# CC_Debugger.net
KiCad netlist of a schematic drawn in EAGLE
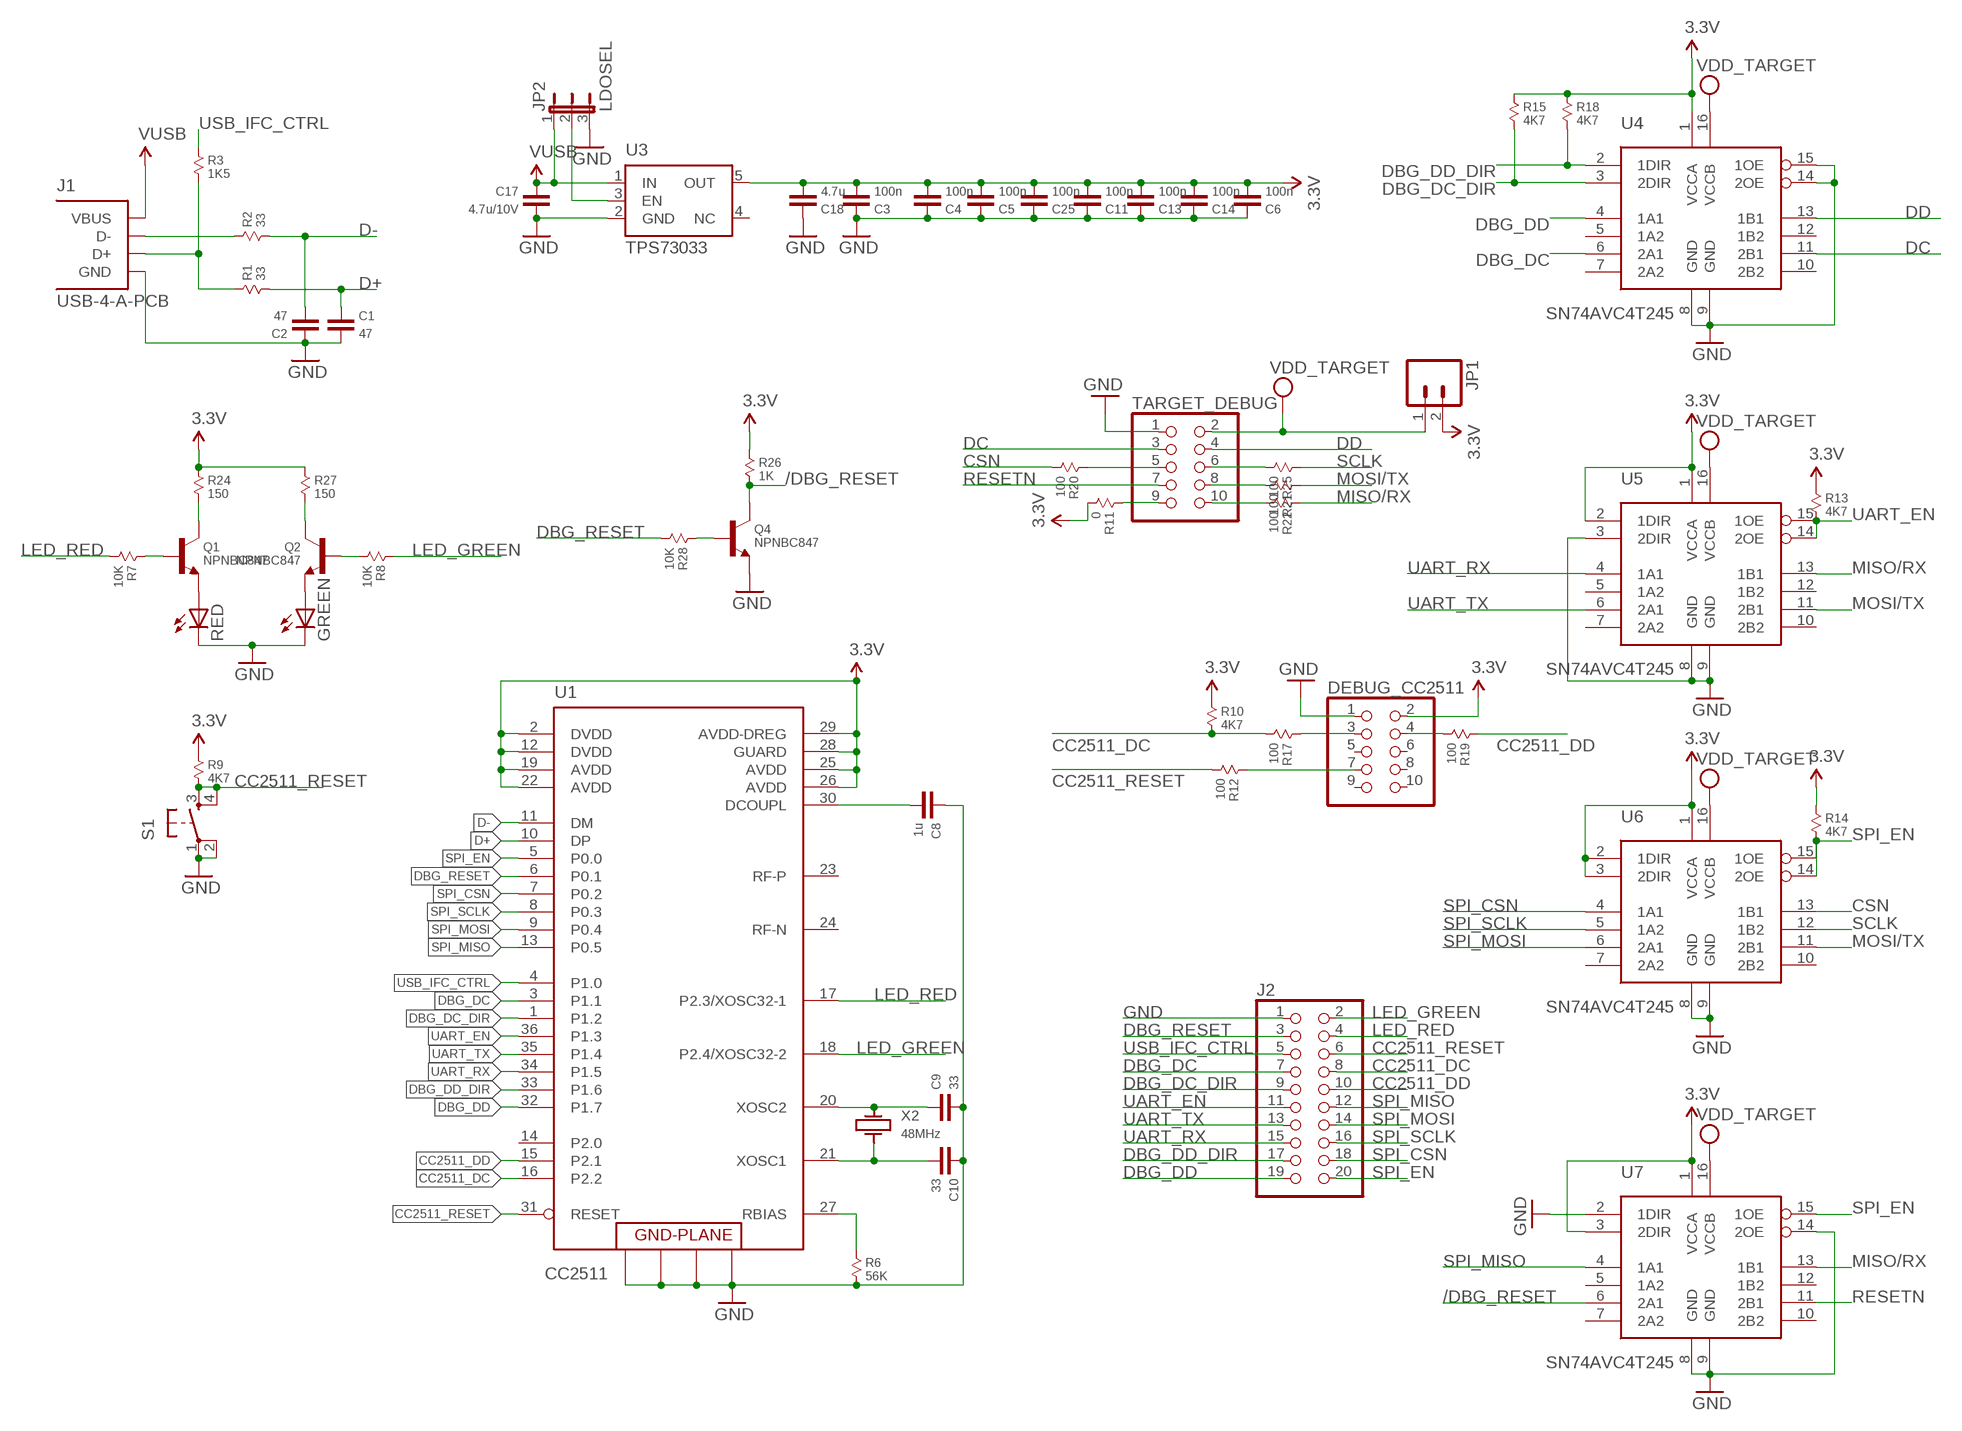
[diagram p0: schematic, sheet 1]

(export (version "E")
  (design (tool "Eeschema 10.0.6"))
  (components
    (comp (ref "C1")
      (value "47")
      (footprint "eagle-import:0603")
      (libsource (lib "eagle-import") (part "CAP-0603"))
    )
    (comp (ref "C2")
      (value "47")
      (footprint "eagle-import:0603")
      (libsource (lib "eagle-import") (part "CAP-0603"))
    )
    (comp (ref "C3")
      (value "100n")
      (footprint "eagle-import:0603")
      (libsource (lib "eagle-import") (part "CAP-0603"))
    )
    (comp (ref "C4")
      (value "100n")
      (footprint "eagle-import:0603")
      (libsource (lib "eagle-import") (part "CAP-0603"))
    )
    (comp (ref "C5")
      (value "100n")
      (footprint "eagle-import:0603")
      (libsource (lib "eagle-import") (part "CAP-0603"))
    )
    (comp (ref "C6")
      (value "100n")
      (footprint "eagle-import:0603")
      (libsource (lib "eagle-import") (part "CAP-0603"))
    )
    (comp (ref "C8")
      (value "1u")
      (footprint "eagle-import:0603")
      (libsource (lib "eagle-import") (part "CAP-0603"))
    )
    (comp (ref "C9")
      (value "33")
      (footprint "eagle-import:0603")
      (libsource (lib "eagle-import") (part "CAP-0603"))
    )
    (comp (ref "C10")
      (value "33")
      (footprint "eagle-import:0603")
      (libsource (lib "eagle-import") (part "CAP-0603"))
    )
    (comp (ref "C11")
      (value "100n")
      (footprint "eagle-import:0603")
      (libsource (lib "eagle-import") (part "CAP-0603"))
    )
    (comp (ref "C13")
      (value "100n")
      (footprint "eagle-import:0603")
      (libsource (lib "eagle-import") (part "CAP-0603"))
    )
    (comp (ref "C14")
      (value "100n")
      (footprint "eagle-import:0603")
      (libsource (lib "eagle-import") (part "CAP-0603"))
    )
    (comp (ref "C17")
      (value "4.7u/10V")
      (footprint "eagle-import:0603")
      (libsource (lib "eagle-import") (part "CAP-0603"))
    )
    (comp (ref "C18")
      (value "4.7u")
      (footprint "eagle-import:0603")
      (libsource (lib "eagle-import") (part "CAP-0603"))
    )
    (comp (ref "C25")
      (value "100n")
      (footprint "eagle-import:0603")
      (libsource (lib "eagle-import") (part "CAP-0603"))
    )
    (comp (ref "DEBUG_CC2511")
      (value "PINHD-2X5")
      (footprint "eagle-import:2X05")
      (libsource (lib "eagle-import") (part "PINHD-2X5"))
    )
    (comp (ref "GREEN")
      (value "LEDCHIPLED_0805")
      (footprint "eagle-import:CHIPLED_0805")
      (libsource (lib "eagle-import") (part "LEDCHIPLED_0805"))
    )
    (comp (ref "J1")
      (value "USB-4-A-PCB")
      (footprint "eagle-import:USB-A-PCB")
      (libsource (lib "eagle-import") (part "USB-4-A-PCB"))
    )
    (comp (ref "J2")
      (value "PINHD-2X10")
      (footprint "eagle-import:2X10")
      (libsource (lib "eagle-import") (part "PINHD-2X10"))
    )
    (comp (ref "JP1")
      (value "M02PTH")
      (footprint "eagle-import:1X02")
      (libsource (lib "eagle-import") (part "M02PTH"))
    )
    (comp (ref "JP2")
      (value "LDOSEL")
      (footprint "eagle-import:SJ_3")
      (libsource (lib "eagle-import") (part "JUMPER-3SMD"))
    )
    (comp (ref "Q1")
      (value "NPNBC847")
      (footprint "eagle-import:SOT-23")
      (libsource (lib "eagle-import") (part "NPNBC847"))
    )
    (comp (ref "Q2")
      (value "NPNBC847")
      (footprint "eagle-import:SOT-23")
      (libsource (lib "eagle-import") (part "NPNBC847"))
    )
    (comp (ref "Q4")
      (value "NPNBC847")
      (footprint "eagle-import:SOT-23")
      (libsource (lib "eagle-import") (part "NPNBC847"))
    )
    (comp (ref "R1")
      (value "33")
      (footprint "eagle-import:0603")
      (libsource (lib "eagle-import") (part "RESISTOR-0603"))
    )
    (comp (ref "R2")
      (value "33")
      (footprint "eagle-import:0603")
      (libsource (lib "eagle-import") (part "RESISTOR-0603"))
    )
    (comp (ref "R3")
      (value "1K5")
      (footprint "eagle-import:0603")
      (libsource (lib "eagle-import") (part "RESISTOR-0603"))
    )
    (comp (ref "R6")
      (value "56K")
      (footprint "eagle-import:0603")
      (libsource (lib "eagle-import") (part "RESISTOR-0603"))
    )
    (comp (ref "R7")
      (value "10K")
      (footprint "eagle-import:0603")
      (libsource (lib "eagle-import") (part "RESISTOR-0603"))
    )
    (comp (ref "R8")
      (value "10K")
      (footprint "eagle-import:0603")
      (libsource (lib "eagle-import") (part "RESISTOR-0603"))
    )
    (comp (ref "R9")
      (value "4K7")
      (footprint "eagle-import:0603")
      (libsource (lib "eagle-import") (part "RESISTOR-0603"))
    )
    (comp (ref "R10")
      (value "4K7")
      (footprint "eagle-import:0603")
      (libsource (lib "eagle-import") (part "RESISTOR-0603"))
    )
    (comp (ref "R11")
      (value "0")
      (footprint "eagle-import:0603")
      (libsource (lib "eagle-import") (part "RESISTOR-0603"))
    )
    (comp (ref "R12")
      (value "100")
      (footprint "eagle-import:0603")
      (libsource (lib "eagle-import") (part "RESISTOR-0603"))
    )
    (comp (ref "R13")
      (value "4K7")
      (footprint "eagle-import:0603")
      (libsource (lib "eagle-import") (part "RESISTOR-0603"))
    )
    (comp (ref "R14")
      (value "4K7")
      (footprint "eagle-import:0603")
      (libsource (lib "eagle-import") (part "RESISTOR-0603"))
    )
    (comp (ref "R15")
      (value "4K7")
      (footprint "eagle-import:0603")
      (libsource (lib "eagle-import") (part "RESISTOR-0603"))
    )
    (comp (ref "R17")
      (value "100")
      (footprint "eagle-import:0603")
      (libsource (lib "eagle-import") (part "RESISTOR-0603"))
    )
    (comp (ref "R18")
      (value "4K7")
      (footprint "eagle-import:0603")
      (libsource (lib "eagle-import") (part "RESISTOR-0603"))
    )
    (comp (ref "R19")
      (value "100")
      (footprint "eagle-import:0603")
      (libsource (lib "eagle-import") (part "RESISTOR-0603"))
    )
    (comp (ref "R20")
      (value "100")
      (footprint "eagle-import:0603")
      (libsource (lib "eagle-import") (part "RESISTOR-0603"))
    )
    (comp (ref "R21")
      (value "100")
      (footprint "eagle-import:0603")
      (libsource (lib "eagle-import") (part "RESISTOR-0603"))
    )
    (comp (ref "R22")
      (value "100")
      (footprint "eagle-import:0603")
      (libsource (lib "eagle-import") (part "RESISTOR-0603"))
    )
    (comp (ref "R24")
      (value "150")
      (footprint "eagle-import:0603")
      (libsource (lib "eagle-import") (part "RESISTOR-0603"))
    )
    (comp (ref "R25")
      (value "100")
      (footprint "eagle-import:0603")
      (libsource (lib "eagle-import") (part "RESISTOR-0603"))
    )
    (comp (ref "R26")
      (value "1K")
      (footprint "eagle-import:0603")
      (libsource (lib "eagle-import") (part "RESISTOR-0603"))
    )
    (comp (ref "R27")
      (value "150")
      (footprint "eagle-import:0603")
      (libsource (lib "eagle-import") (part "RESISTOR-0603"))
    )
    (comp (ref "R28")
      (value "10K")
      (footprint "eagle-import:0603")
      (libsource (lib "eagle-import") (part "RESISTOR-0603"))
    )
    (comp (ref "RED")
      (value "LEDCHIPLED_0805")
      (footprint "eagle-import:CHIPLED_0805")
      (libsource (lib "eagle-import") (part "LEDCHIPLED_0805"))
    )
    (comp (ref "S1")
      (value "TAC_SWITCHPTH")
      (footprint "eagle-import:TACTILE-PTH")
      (libsource (lib "eagle-import") (part "TAC_SWITCHPTH"))
    )
    (comp (ref "TARGET_DEBUG")
      (value "PINHD-2X5")
      (footprint "eagle-import:2X05")
      (libsource (lib "eagle-import") (part "PINHD-2X5"))
    )
    (comp (ref "U1")
      (value "CC2511")
      (footprint "eagle-import:QLP-36")
      (libsource (lib "eagle-import") (part "CC2511"))
    )
    (comp (ref "U3")
      (value "TPS73033")
      (footprint "eagle-import:SOT23-5")
      (libsource (lib "eagle-import") (part "TPS73033"))
    )
    (comp (ref "U4")
      (value "SN74AVC4T245")
      (footprint "eagle-import:TSSOP16")
      (libsource (lib "eagle-import") (part "SN74AVC4T245"))
    )
    (comp (ref "U5")
      (value "SN74AVC4T245")
      (footprint "eagle-import:TSSOP16")
      (libsource (lib "eagle-import") (part "SN74AVC4T245"))
    )
    (comp (ref "U6")
      (value "SN74AVC4T245")
      (footprint "eagle-import:TSSOP16")
      (libsource (lib "eagle-import") (part "SN74AVC4T245"))
    )
    (comp (ref "U7")
      (value "SN74AVC4T245")
      (footprint "eagle-import:TSSOP16")
      (libsource (lib "eagle-import") (part "SN74AVC4T245"))
    )
    (comp (ref "X2")
      (value "48MHz")
      (footprint "eagle-import:KX-9A")
      (libsource (lib "eagle-import") (part "CRYSTAL-KX-9A"))
    )
  )
  (nets
    (net (code "1") (name "/CSN") (class "Default")
      (node (ref "R20") (pin "2") (pinfunction "2_2") (pintype "passive"))
      (node (ref "U6") (pin "13") (pinfunction "1B1_13") (pintype "bidirectional"))
    )
    (net (code "2") (name "/DC") (class "Default")
      (node (ref "TARGET_DEBUG") (pin "3") (pinfunction "3_3") (pintype "passive"))
      (node (ref "U4") (pin "11") (pinfunction "2B1_11") (pintype "bidirectional"))
    )
    (net (code "3") (name "/DD") (class "Default")
      (node (ref "TARGET_DEBUG") (pin "4") (pinfunction "4_4") (pintype "passive"))
      (node (ref "U4") (pin "13") (pinfunction "1B1_13") (pintype "bidirectional"))
    )
    (net (code "4") (name "/LED_GREEN") (class "Default")
      (node (ref "J2") (pin "2") (pinfunction "2_2") (pintype "passive"))
      (node (ref "R8") (pin "1") (pinfunction "1_1") (pintype "passive"))
      (node (ref "U1") (pin "18") (pinfunction "P2.4/XOSC32-2_18") (pintype "passive"))
    )
    (net (code "5") (name "/LED_RED") (class "Default")
      (node (ref "J2") (pin "4") (pinfunction "4_4") (pintype "passive"))
      (node (ref "R7") (pin "2") (pinfunction "2_2") (pintype "passive"))
      (node (ref "U1") (pin "17") (pinfunction "P2.3/XOSC32-1_17") (pintype "passive"))
    )
    (net (code "6") (name "/MISO{slash}RX") (class "Default")
      (node (ref "R22") (pin "1") (pinfunction "1_1") (pintype "passive"))
      (node (ref "U5") (pin "13") (pinfunction "1B1_13") (pintype "bidirectional"))
      (node (ref "U7") (pin "13") (pinfunction "1B1_13") (pintype "bidirectional"))
    )
    (net (code "7") (name "/MOSI{slash}TX") (class "Default")
      (node (ref "R21") (pin "1") (pinfunction "1_1") (pintype "passive"))
      (node (ref "U5") (pin "11") (pinfunction "2B1_11") (pintype "bidirectional"))
      (node (ref "U6") (pin "11") (pinfunction "2B1_11") (pintype "bidirectional"))
    )
    (net (code "8") (name "/RESETN") (class "Default")
      (node (ref "TARGET_DEBUG") (pin "7") (pinfunction "7_7") (pintype "passive"))
      (node (ref "U7") (pin "11") (pinfunction "2B1_11") (pintype "bidirectional"))
    )
    (net (code "9") (name "/SCLK") (class "Default")
      (node (ref "R25") (pin "1") (pinfunction "1_1") (pintype "passive"))
      (node (ref "U6") (pin "12") (pinfunction "1B2_12") (pintype "bidirectional"))
    )
    (net (code "10") (name "/{slash}DBG_RESET") (class "Default")
      (node (ref "Q4") (pin "3") (pinfunction "C_3") (pintype "passive"))
      (node (ref "R26") (pin "2") (pinfunction "2_2") (pintype "passive"))
      (node (ref "U7") (pin "6") (pinfunction "2A1_6") (pintype "bidirectional"))
    )
    (net (code "11") (name "3.3V") (class "Default")
      (node (ref "C11") (pin "1") (pinfunction "1_1") (pintype "passive"))
      (node (ref "C13") (pin "1") (pinfunction "1_1") (pintype "passive"))
      (node (ref "C14") (pin "1") (pinfunction "1_1") (pintype "passive"))
      (node (ref "C18") (pin "1") (pinfunction "1_1") (pintype "passive"))
      (node (ref "C25") (pin "1") (pinfunction "1_1") (pintype "passive"))
      (node (ref "C3") (pin "1") (pinfunction "1_1") (pintype "passive"))
      (node (ref "C4") (pin "1") (pinfunction "1_1") (pintype "passive"))
      (node (ref "C5") (pin "1") (pinfunction "1_1") (pintype "passive"))
      (node (ref "C6") (pin "1") (pinfunction "1_1") (pintype "passive"))
      (node (ref "DEBUG_CC2511") (pin "2") (pinfunction "2_2") (pintype "passive"))
      (node (ref "JP1") (pin "2") (pinfunction "2_2") (pintype "passive"))
      (node (ref "R10") (pin "1") (pinfunction "1_1") (pintype "passive"))
      (node (ref "R11") (pin "2") (pinfunction "2_2") (pintype "passive"))
      (node (ref "R13") (pin "1") (pinfunction "1_1") (pintype "passive"))
      (node (ref "R14") (pin "1") (pinfunction "1_1") (pintype "passive"))
      (node (ref "R15") (pin "1") (pinfunction "1_1") (pintype "passive"))
      (node (ref "R18") (pin "1") (pinfunction "1_1") (pintype "passive"))
      (node (ref "R24") (pin "1") (pinfunction "1_1") (pintype "passive"))
      (node (ref "R26") (pin "1") (pinfunction "1_1") (pintype "passive"))
      (node (ref "R27") (pin "1") (pinfunction "1_1") (pintype "passive"))
      (node (ref "R9") (pin "1") (pinfunction "1_1") (pintype "passive"))
      (node (ref "U1") (pin "12") (pinfunction "DVDD_12") (pintype "passive"))
      (node (ref "U1") (pin "19") (pinfunction "AVDD_19") (pintype "passive"))
      (node (ref "U1") (pin "2") (pinfunction "DVDD_2") (pintype "passive"))
      (node (ref "U1") (pin "22") (pinfunction "AVDD_22") (pintype "passive"))
      (node (ref "U1") (pin "25") (pinfunction "AVDD_25") (pintype "passive"))
      (node (ref "U1") (pin "26") (pinfunction "AVDD_26") (pintype "passive"))
      (node (ref "U1") (pin "28") (pinfunction "GUARD_28") (pintype "passive"))
      (node (ref "U1") (pin "29") (pinfunction "AVDD-DREG_29") (pintype "passive"))
      (node (ref "U3") (pin "5") (pinfunction "OUT_5") (pintype "passive"))
      (node (ref "U4") (pin "1") (pinfunction "VCCA_1") (pintype "passive"))
      (node (ref "U5") (pin "1") (pinfunction "VCCA_1") (pintype "passive"))
      (node (ref "U5") (pin "2") (pinfunction "1DIR_2") (pintype "input"))
      (node (ref "U6") (pin "1") (pinfunction "VCCA_1") (pintype "passive"))
      (node (ref "U6") (pin "2") (pinfunction "1DIR_2") (pintype "input"))
      (node (ref "U6") (pin "3") (pinfunction "2DIR_3") (pintype "input"))
      (node (ref "U7") (pin "1") (pinfunction "VCCA_1") (pintype "passive"))
      (node (ref "U7") (pin "3") (pinfunction "2DIR_3") (pintype "input"))
    )
    (net (code "12") (name "CC2511_DC") (class "Default")
      (node (ref "J2") (pin "8") (pinfunction "8_8") (pintype "passive"))
      (node (ref "R10") (pin "2") (pinfunction "2_2") (pintype "passive"))
      (node (ref "R17") (pin "2") (pinfunction "2_2") (pintype "passive"))
      (node (ref "U1") (pin "16") (pinfunction "P2.2_16") (pintype "bidirectional"))
    )
    (net (code "13") (name "CC2511_DD") (class "Default")
      (node (ref "J2") (pin "10") (pinfunction "10_10") (pintype "passive"))
      (node (ref "R19") (pin "1") (pinfunction "1_1") (pintype "passive"))
      (node (ref "U1") (pin "15") (pinfunction "P2.1_15") (pintype "bidirectional"))
    )
    (net (code "14") (name "CC2511_RESET") (class "Default")
      (node (ref "J2") (pin "6") (pinfunction "6_6") (pintype "passive"))
      (node (ref "R12") (pin "2") (pinfunction "2_2") (pintype "passive"))
      (node (ref "R9") (pin "2") (pinfunction "2_2") (pintype "passive"))
      (node (ref "S1") (pin "3") (pinfunction "3_3") (pintype "passive"))
      (node (ref "S1") (pin "4") (pinfunction "4_4") (pintype "passive"))
      (node (ref "U1") (pin "31") (pinfunction "RESET_31") (pintype "input"))
    )
    (net (code "15") (name "D+") (class "Default")
      (node (ref "C1") (pin "2") (pinfunction "2_2") (pintype "passive"))
      (node (ref "R1") (pin "2") (pinfunction "2_2") (pintype "passive"))
      (node (ref "U1") (pin "10") (pinfunction "DP_10") (pintype "bidirectional"))
    )
    (net (code "16") (name "D-") (class "Default")
      (node (ref "C2") (pin "1") (pinfunction "1_1") (pintype "passive"))
      (node (ref "R2") (pin "2") (pinfunction "2_2") (pintype "passive"))
      (node (ref "U1") (pin "11") (pinfunction "DM_11") (pintype "bidirectional"))
    )
    (net (code "17") (name "DBG_DC") (class "Default")
      (node (ref "J2") (pin "7") (pinfunction "7_7") (pintype "passive"))
      (node (ref "U1") (pin "3") (pinfunction "P1.1_3") (pintype "bidirectional"))
      (node (ref "U4") (pin "6") (pinfunction "2A1_6") (pintype "bidirectional"))
    )
    (net (code "18") (name "DBG_DC_DIR") (class "Default")
      (node (ref "J2") (pin "9") (pinfunction "9_9") (pintype "passive"))
      (node (ref "R15") (pin "2") (pinfunction "2_2") (pintype "passive"))
      (node (ref "U1") (pin "1") (pinfunction "P1.2_1") (pintype "bidirectional"))
      (node (ref "U4") (pin "3") (pinfunction "2DIR_3") (pintype "input"))
    )
    (net (code "19") (name "DBG_DD") (class "Default")
      (node (ref "J2") (pin "19") (pinfunction "19_19") (pintype "passive"))
      (node (ref "U1") (pin "32") (pinfunction "P1.7_32") (pintype "bidirectional"))
      (node (ref "U4") (pin "4") (pinfunction "1A1_4") (pintype "bidirectional"))
    )
    (net (code "20") (name "DBG_DD_DIR") (class "Default")
      (node (ref "J2") (pin "17") (pinfunction "17_17") (pintype "passive"))
      (node (ref "R18") (pin "2") (pinfunction "2_2") (pintype "passive"))
      (node (ref "U1") (pin "33") (pinfunction "P1.6_33") (pintype "bidirectional"))
      (node (ref "U4") (pin "2") (pinfunction "1DIR_2") (pintype "input"))
    )
    (net (code "21") (name "DBG_RESET") (class "Default")
      (node (ref "J2") (pin "3") (pinfunction "3_3") (pintype "passive"))
      (node (ref "R28") (pin "2") (pinfunction "2_2") (pintype "passive"))
      (node (ref "U1") (pin "6") (pinfunction "P0.1_6") (pintype "bidirectional"))
    )
    (net (code "22") (name "GND") (class "Default")
      (node (ref "C1") (pin "1") (pinfunction "1_1") (pintype "passive"))
      (node (ref "C10") (pin "2") (pinfunction "2_2") (pintype "passive"))
      (node (ref "C11") (pin "2") (pinfunction "2_2") (pintype "passive"))
      (node (ref "C13") (pin "2") (pinfunction "2_2") (pintype "passive"))
      (node (ref "C14") (pin "2") (pinfunction "2_2") (pintype "passive"))
      (node (ref "C17") (pin "1") (pinfunction "1_1") (pintype "passive"))
      (node (ref "C18") (pin "2") (pinfunction "2_2") (pintype "passive"))
      (node (ref "C2") (pin "2") (pinfunction "2_2") (pintype "passive"))
      (node (ref "C25") (pin "2") (pinfunction "2_2") (pintype "passive"))
      (node (ref "C3") (pin "2") (pinfunction "2_2") (pintype "passive"))
      (node (ref "C4") (pin "2") (pinfunction "2_2") (pintype "passive"))
      (node (ref "C5") (pin "2") (pinfunction "2_2") (pintype "passive"))
      (node (ref "C6") (pin "2") (pinfunction "2_2") (pintype "passive"))
      (node (ref "C8") (pin "2") (pinfunction "2_2") (pintype "passive"))
      (node (ref "C9") (pin "1") (pinfunction "1_1") (pintype "passive"))
      (node (ref "DEBUG_CC2511") (pin "1") (pinfunction "1_1") (pintype "passive"))
      (node (ref "GREEN") (pin "C") (pinfunction "C_C") (pintype "passive"))
      (node (ref "J1") (pin "GND") (pinfunction "GND_GND") (pintype "power_in"))
      (node (ref "J2") (pin "1") (pinfunction "1_1") (pintype "passive"))
      (node (ref "JP2") (pin "3") (pinfunction "3_3") (pintype "passive"))
      (node (ref "Q4") (pin "2") (pinfunction "E_2") (pintype "passive"))
      (node (ref "R6") (pin "2") (pinfunction "2_2") (pintype "passive"))
      (node (ref "RED") (pin "C") (pinfunction "C_C") (pintype "passive"))
      (node (ref "S1") (pin "1") (pinfunction "1_1") (pintype "passive"))
      (node (ref "S1") (pin "2") (pinfunction "2_2") (pintype "passive"))
      (node (ref "TARGET_DEBUG") (pin "1") (pinfunction "1_1") (pintype "passive"))
      (node (ref "U1") (pin "37") (pinfunction "GND_37") (pintype "power_in"))
      (node (ref "U1") (pin "38") (pinfunction "GND_38") (pintype "power_in"))
      (node (ref "U1") (pin "39") (pinfunction "GND_39") (pintype "power_in"))
      (node (ref "U1") (pin "40") (pinfunction "GND_40") (pintype "power_in"))
      (node (ref "U3") (pin "2") (pinfunction "GND_2") (pintype "power_in"))
      (node (ref "U4") (pin "14") (pinfunction "2OE_14") (pintype "input"))
      (node (ref "U4") (pin "15") (pinfunction "1OE_15") (pintype "input"))
      (node (ref "U4") (pin "8") (pinfunction "GND_8") (pintype "power_in"))
      (node (ref "U4") (pin "9") (pinfunction "GND_9") (pintype "bidirectional"))
      (node (ref "U5") (pin "3") (pinfunction "2DIR_3") (pintype "input"))
      (node (ref "U5") (pin "8") (pinfunction "GND_8") (pintype "power_in"))
      (node (ref "U5") (pin "9") (pinfunction "GND_9") (pintype "bidirectional"))
      (node (ref "U6") (pin "8") (pinfunction "GND_8") (pintype "power_in"))
      (node (ref "U6") (pin "9") (pinfunction "GND_9") (pintype "bidirectional"))
      (node (ref "U7") (pin "14") (pinfunction "2OE_14") (pintype "input"))
      (node (ref "U7") (pin "2") (pinfunction "1DIR_2") (pintype "input"))
      (node (ref "U7") (pin "8") (pinfunction "GND_8") (pintype "power_in"))
      (node (ref "U7") (pin "9") (pinfunction "GND_9") (pintype "bidirectional"))
    )
    (net (code "23") (name "Net-(DEBUG_CC2511-Pad3)") (class "Default")
      (node (ref "DEBUG_CC2511") (pin "3") (pinfunction "3_3") (pintype "passive"))
      (node (ref "R17") (pin "1") (pinfunction "1_1") (pintype "passive"))
    )
    (net (code "24") (name "Net-(DEBUG_CC2511-Pad4)") (class "Default")
      (node (ref "DEBUG_CC2511") (pin "4") (pinfunction "4_4") (pintype "passive"))
      (node (ref "R19") (pin "2") (pinfunction "2_2") (pintype "passive"))
    )
    (net (code "25") (name "Net-(DEBUG_CC2511-Pad7)") (class "Default")
      (node (ref "DEBUG_CC2511") (pin "7") (pinfunction "7_7") (pintype "passive"))
      (node (ref "R12") (pin "1") (pinfunction "1_1") (pintype "passive"))
    )
    (net (code "26") (name "Net-(J1-PadD+)") (class "Default")
      (node (ref "J1") (pin "D+") (pinfunction "D+_D+") (pintype "bidirectional"))
      (node (ref "R1") (pin "1") (pinfunction "1_1") (pintype "passive"))
      (node (ref "R3") (pin "2") (pinfunction "2_2") (pintype "passive"))
    )
    (net (code "27") (name "Net-(J1-PadD-)") (class "Default")
      (node (ref "J1") (pin "D-") (pinfunction "D-_D-") (pintype "bidirectional"))
      (node (ref "R2") (pin "1") (pinfunction "1_1") (pintype "passive"))
    )
    (net (code "28") (name "Net-(Q1-B)") (class "Default")
      (node (ref "Q1") (pin "1") (pinfunction "B_1") (pintype "passive"))
      (node (ref "R7") (pin "1") (pinfunction "1_1") (pintype "passive"))
    )
    (net (code "29") (name "Net-(Q1-C)") (class "Default")
      (node (ref "Q1") (pin "3") (pinfunction "C_3") (pintype "passive"))
      (node (ref "R24") (pin "2") (pinfunction "2_2") (pintype "passive"))
    )
    (net (code "30") (name "Net-(Q1-E)") (class "Default")
      (node (ref "Q1") (pin "2") (pinfunction "E_2") (pintype "passive"))
      (node (ref "RED") (pin "A") (pinfunction "A_A") (pintype "passive"))
    )
    (net (code "31") (name "Net-(Q2-B)") (class "Default")
      (node (ref "Q2") (pin "1") (pinfunction "B_1") (pintype "passive"))
      (node (ref "R8") (pin "2") (pinfunction "2_2") (pintype "passive"))
    )
    (net (code "32") (name "Net-(Q2-C)") (class "Default")
      (node (ref "Q2") (pin "3") (pinfunction "C_3") (pintype "passive"))
      (node (ref "R27") (pin "2") (pinfunction "2_2") (pintype "passive"))
    )
    (net (code "33") (name "Net-(Q2-E)") (class "Default")
      (node (ref "GREEN") (pin "A") (pinfunction "A_A") (pintype "passive"))
      (node (ref "Q2") (pin "2") (pinfunction "E_2") (pintype "passive"))
    )
    (net (code "34") (name "Net-(Q4-B)") (class "Default")
      (node (ref "Q4") (pin "1") (pinfunction "B_1") (pintype "passive"))
      (node (ref "R28") (pin "1") (pinfunction "1_1") (pintype "passive"))
    )
    (net (code "35") (name "Net-(R11-Pad1)") (class "Default")
      (node (ref "R11") (pin "1") (pinfunction "1_1") (pintype "passive"))
      (node (ref "TARGET_DEBUG") (pin "9") (pinfunction "9_9") (pintype "passive"))
    )
    (net (code "36") (name "Net-(R20-Pad1)") (class "Default")
      (node (ref "R20") (pin "1") (pinfunction "1_1") (pintype "passive"))
      (node (ref "TARGET_DEBUG") (pin "5") (pinfunction "5_5") (pintype "passive"))
    )
    (net (code "37") (name "Net-(R21-Pad2)") (class "Default")
      (node (ref "R21") (pin "2") (pinfunction "2_2") (pintype "passive"))
      (node (ref "TARGET_DEBUG") (pin "8") (pinfunction "8_8") (pintype "passive"))
    )
    (net (code "38") (name "Net-(R22-Pad2)") (class "Default")
      (node (ref "R22") (pin "2") (pinfunction "2_2") (pintype "passive"))
      (node (ref "TARGET_DEBUG") (pin "10") (pinfunction "10_10") (pintype "passive"))
    )
    (net (code "39") (name "Net-(R25-Pad2)") (class "Default")
      (node (ref "R25") (pin "2") (pinfunction "2_2") (pintype "passive"))
      (node (ref "TARGET_DEBUG") (pin "6") (pinfunction "6_6") (pintype "passive"))
    )
    (net (code "40") (name "Net-(U1-DCOUPL)") (class "Default")
      (node (ref "C8") (pin "1") (pinfunction "1_1") (pintype "passive"))
      (node (ref "U1") (pin "30") (pinfunction "DCOUPL_30") (pintype "passive"))
    )
    (net (code "41") (name "Net-(U1-RBIAS)") (class "Default")
      (node (ref "R6") (pin "1") (pinfunction "1_1") (pintype "passive"))
      (node (ref "U1") (pin "27") (pinfunction "RBIAS_27") (pintype "passive"))
    )
    (net (code "42") (name "Net-(U1-XOSC1)") (class "Default")
      (node (ref "C10") (pin "1") (pinfunction "1_1") (pintype "passive"))
      (node (ref "U1") (pin "21") (pinfunction "XOSC1_21") (pintype "passive"))
      (node (ref "X2") (pin "3") (pinfunction "2_3") (pintype "passive"))
    )
    (net (code "43") (name "Net-(U1-XOSC2)") (class "Default")
      (node (ref "C9") (pin "2") (pinfunction "2_2") (pintype "passive"))
      (node (ref "U1") (pin "20") (pinfunction "XOSC2_20") (pintype "passive"))
      (node (ref "X2") (pin "1") (pinfunction "1_1") (pintype "passive"))
    )
    (net (code "44") (name "Net-(U3-EN)") (class "Default")
      (node (ref "JP2") (pin "2") (pinfunction "2_2") (pintype "passive"))
      (node (ref "U3") (pin "3") (pinfunction "EN_3") (pintype "input"))
    )
    (net (code "45") (name "SPI_CSN") (class "Default")
      (node (ref "J2") (pin "18") (pinfunction "18_18") (pintype "passive"))
      (node (ref "U1") (pin "7") (pinfunction "P0.2_7") (pintype "bidirectional"))
      (node (ref "U6") (pin "4") (pinfunction "1A1_4") (pintype "bidirectional"))
    )
    (net (code "46") (name "SPI_EN") (class "Default")
      (node (ref "J2") (pin "20") (pinfunction "20_20") (pintype "passive"))
      (node (ref "R14") (pin "2") (pinfunction "2_2") (pintype "passive"))
      (node (ref "U1") (pin "5") (pinfunction "P0.0_5") (pintype "bidirectional"))
      (node (ref "U6") (pin "14") (pinfunction "2OE_14") (pintype "input"))
      (node (ref "U6") (pin "15") (pinfunction "1OE_15") (pintype "input"))
      (node (ref "U7") (pin "15") (pinfunction "1OE_15") (pintype "input"))
    )
    (net (code "47") (name "SPI_MISO") (class "Default")
      (node (ref "J2") (pin "12") (pinfunction "12_12") (pintype "passive"))
      (node (ref "U1") (pin "13") (pinfunction "P0.5_13") (pintype "bidirectional"))
      (node (ref "U7") (pin "4") (pinfunction "1A1_4") (pintype "bidirectional"))
    )
    (net (code "48") (name "SPI_MOSI") (class "Default")
      (node (ref "J2") (pin "14") (pinfunction "14_14") (pintype "passive"))
      (node (ref "U1") (pin "9") (pinfunction "P0.4_9") (pintype "bidirectional"))
      (node (ref "U6") (pin "6") (pinfunction "2A1_6") (pintype "bidirectional"))
    )
    (net (code "49") (name "SPI_SCLK") (class "Default")
      (node (ref "J2") (pin "16") (pinfunction "16_16") (pintype "passive"))
      (node (ref "U1") (pin "8") (pinfunction "P0.3_8") (pintype "bidirectional"))
      (node (ref "U6") (pin "5") (pinfunction "1A2_5") (pintype "bidirectional"))
    )
    (net (code "50") (name "UART_EN") (class "Default")
      (node (ref "J2") (pin "11") (pinfunction "11_11") (pintype "passive"))
      (node (ref "R13") (pin "2") (pinfunction "2_2") (pintype "passive"))
      (node (ref "U1") (pin "36") (pinfunction "P1.3_36") (pintype "bidirectional"))
      (node (ref "U5") (pin "14") (pinfunction "2OE_14") (pintype "input"))
      (node (ref "U5") (pin "15") (pinfunction "1OE_15") (pintype "input"))
    )
    (net (code "51") (name "UART_RX") (class "Default")
      (node (ref "J2") (pin "15") (pinfunction "15_15") (pintype "passive"))
      (node (ref "U1") (pin "34") (pinfunction "P1.5_34") (pintype "bidirectional"))
      (node (ref "U5") (pin "4") (pinfunction "1A1_4") (pintype "bidirectional"))
    )
    (net (code "52") (name "UART_TX") (class "Default")
      (node (ref "J2") (pin "13") (pinfunction "13_13") (pintype "passive"))
      (node (ref "U1") (pin "35") (pinfunction "P1.4_35") (pintype "bidirectional"))
      (node (ref "U5") (pin "6") (pinfunction "2A1_6") (pintype "bidirectional"))
    )
    (net (code "53") (name "USB_IFC_CTRL") (class "Default")
      (node (ref "J2") (pin "5") (pinfunction "5_5") (pintype "passive"))
      (node (ref "R3") (pin "1") (pinfunction "1_1") (pintype "passive"))
      (node (ref "U1") (pin "4") (pinfunction "P1.0_4") (pintype "bidirectional"))
    )
    (net (code "54") (name "VDD_TARGET") (class "Default")
      (node (ref "JP1") (pin "1") (pinfunction "1_1") (pintype "passive"))
      (node (ref "TARGET_DEBUG") (pin "2") (pinfunction "2_2") (pintype "passive"))
      (node (ref "U4") (pin "16") (pinfunction "VCCB_16") (pintype "passive"))
      (node (ref "U5") (pin "16") (pinfunction "VCCB_16") (pintype "passive"))
      (node (ref "U6") (pin "16") (pinfunction "VCCB_16") (pintype "passive"))
      (node (ref "U7") (pin "16") (pinfunction "VCCB_16") (pintype "passive"))
    )
    (net (code "55") (name "VUSB") (class "Default")
      (node (ref "C17") (pin "2") (pinfunction "2_2") (pintype "passive"))
      (node (ref "J1") (pin "VUSB") (pinfunction "VBUS_VUSB") (pintype "passive"))
      (node (ref "JP2") (pin "1") (pinfunction "1_1") (pintype "passive"))
      (node (ref "U3") (pin "1") (pinfunction "IN_1") (pintype "passive"))
    )
    (net (code "56") (name "unconnected-(DEBUG_CC2511-Pad5)") (class "Default")
      (node (ref "DEBUG_CC2511") (pin "5") (pinfunction "5_5") (pintype "passive"))
    )
    (net (code "57") (name "unconnected-(DEBUG_CC2511-Pad6)") (class "Default")
      (node (ref "DEBUG_CC2511") (pin "6") (pinfunction "6_6") (pintype "passive"))
    )
    (net (code "58") (name "unconnected-(DEBUG_CC2511-Pad8)") (class "Default")
      (node (ref "DEBUG_CC2511") (pin "8") (pinfunction "8_8") (pintype "passive"))
    )
    (net (code "59") (name "unconnected-(DEBUG_CC2511-Pad9)") (class "Default")
      (node (ref "DEBUG_CC2511") (pin "9") (pinfunction "9_9") (pintype "passive"))
    )
    (net (code "60") (name "unconnected-(DEBUG_CC2511-Pad10)") (class "Default")
      (node (ref "DEBUG_CC2511") (pin "10") (pinfunction "10_10") (pintype "passive"))
    )
    (net (code "61") (name "unconnected-(U1-P2.0-Pad14)") (class "Default")
      (node (ref "U1") (pin "14") (pinfunction "P2.0_14") (pintype "bidirectional"))
    )
    (net (code "62") (name "unconnected-(U1-RF-N-Pad24)") (class "Default")
      (node (ref "U1") (pin "24") (pinfunction "RF-N_24") (pintype "passive"))
    )
    (net (code "63") (name "unconnected-(U1-RF-P-Pad23)") (class "Default")
      (node (ref "U1") (pin "23") (pinfunction "RF-P_23") (pintype "passive"))
    )
    (net (code "64") (name "unconnected-(U3-NC-Pad4)") (class "Default")
      (node (ref "U3") (pin "4") (pinfunction "NC_4") (pintype "no_connect"))
    )
    (net (code "65") (name "unconnected-(U4-1A2-Pad5)") (class "Default")
      (node (ref "U4") (pin "5") (pinfunction "1A2_5") (pintype "bidirectional"))
    )
    (net (code "66") (name "unconnected-(U4-1B2-Pad12)") (class "Default")
      (node (ref "U4") (pin "12") (pinfunction "1B2_12") (pintype "bidirectional"))
    )
    (net (code "67") (name "unconnected-(U4-2A2-Pad7)") (class "Default")
      (node (ref "U4") (pin "7") (pinfunction "2A2_7") (pintype "bidirectional"))
    )
    (net (code "68") (name "unconnected-(U4-2B2-Pad10)") (class "Default")
      (node (ref "U4") (pin "10") (pinfunction "2B2_10") (pintype "bidirectional"))
    )
    (net (code "69") (name "unconnected-(U5-1A2-Pad5)") (class "Default")
      (node (ref "U5") (pin "5") (pinfunction "1A2_5") (pintype "bidirectional"))
    )
    (net (code "70") (name "unconnected-(U5-1B2-Pad12)") (class "Default")
      (node (ref "U5") (pin "12") (pinfunction "1B2_12") (pintype "bidirectional"))
    )
    (net (code "71") (name "unconnected-(U5-2A2-Pad7)") (class "Default")
      (node (ref "U5") (pin "7") (pinfunction "2A2_7") (pintype "bidirectional"))
    )
    (net (code "72") (name "unconnected-(U5-2B2-Pad10)") (class "Default")
      (node (ref "U5") (pin "10") (pinfunction "2B2_10") (pintype "bidirectional"))
    )
    (net (code "73") (name "unconnected-(U6-2A2-Pad7)") (class "Default")
      (node (ref "U6") (pin "7") (pinfunction "2A2_7") (pintype "bidirectional"))
    )
    (net (code "74") (name "unconnected-(U6-2B2-Pad10)") (class "Default")
      (node (ref "U6") (pin "10") (pinfunction "2B2_10") (pintype "bidirectional"))
    )
    (net (code "75") (name "unconnected-(U7-1A2-Pad5)") (class "Default")
      (node (ref "U7") (pin "5") (pinfunction "1A2_5") (pintype "bidirectional"))
    )
    (net (code "76") (name "unconnected-(U7-1B2-Pad12)") (class "Default")
      (node (ref "U7") (pin "12") (pinfunction "1B2_12") (pintype "bidirectional"))
    )
    (net (code "77") (name "unconnected-(U7-2A2-Pad7)") (class "Default")
      (node (ref "U7") (pin "7") (pinfunction "2A2_7") (pintype "bidirectional"))
    )
    (net (code "78") (name "unconnected-(U7-2B2-Pad10)") (class "Default")
      (node (ref "U7") (pin "10") (pinfunction "2B2_10") (pintype "bidirectional"))
    )
  )
)
